# LED_Readout.net
KiCad netlist of a schematic drawn in Altium Designer
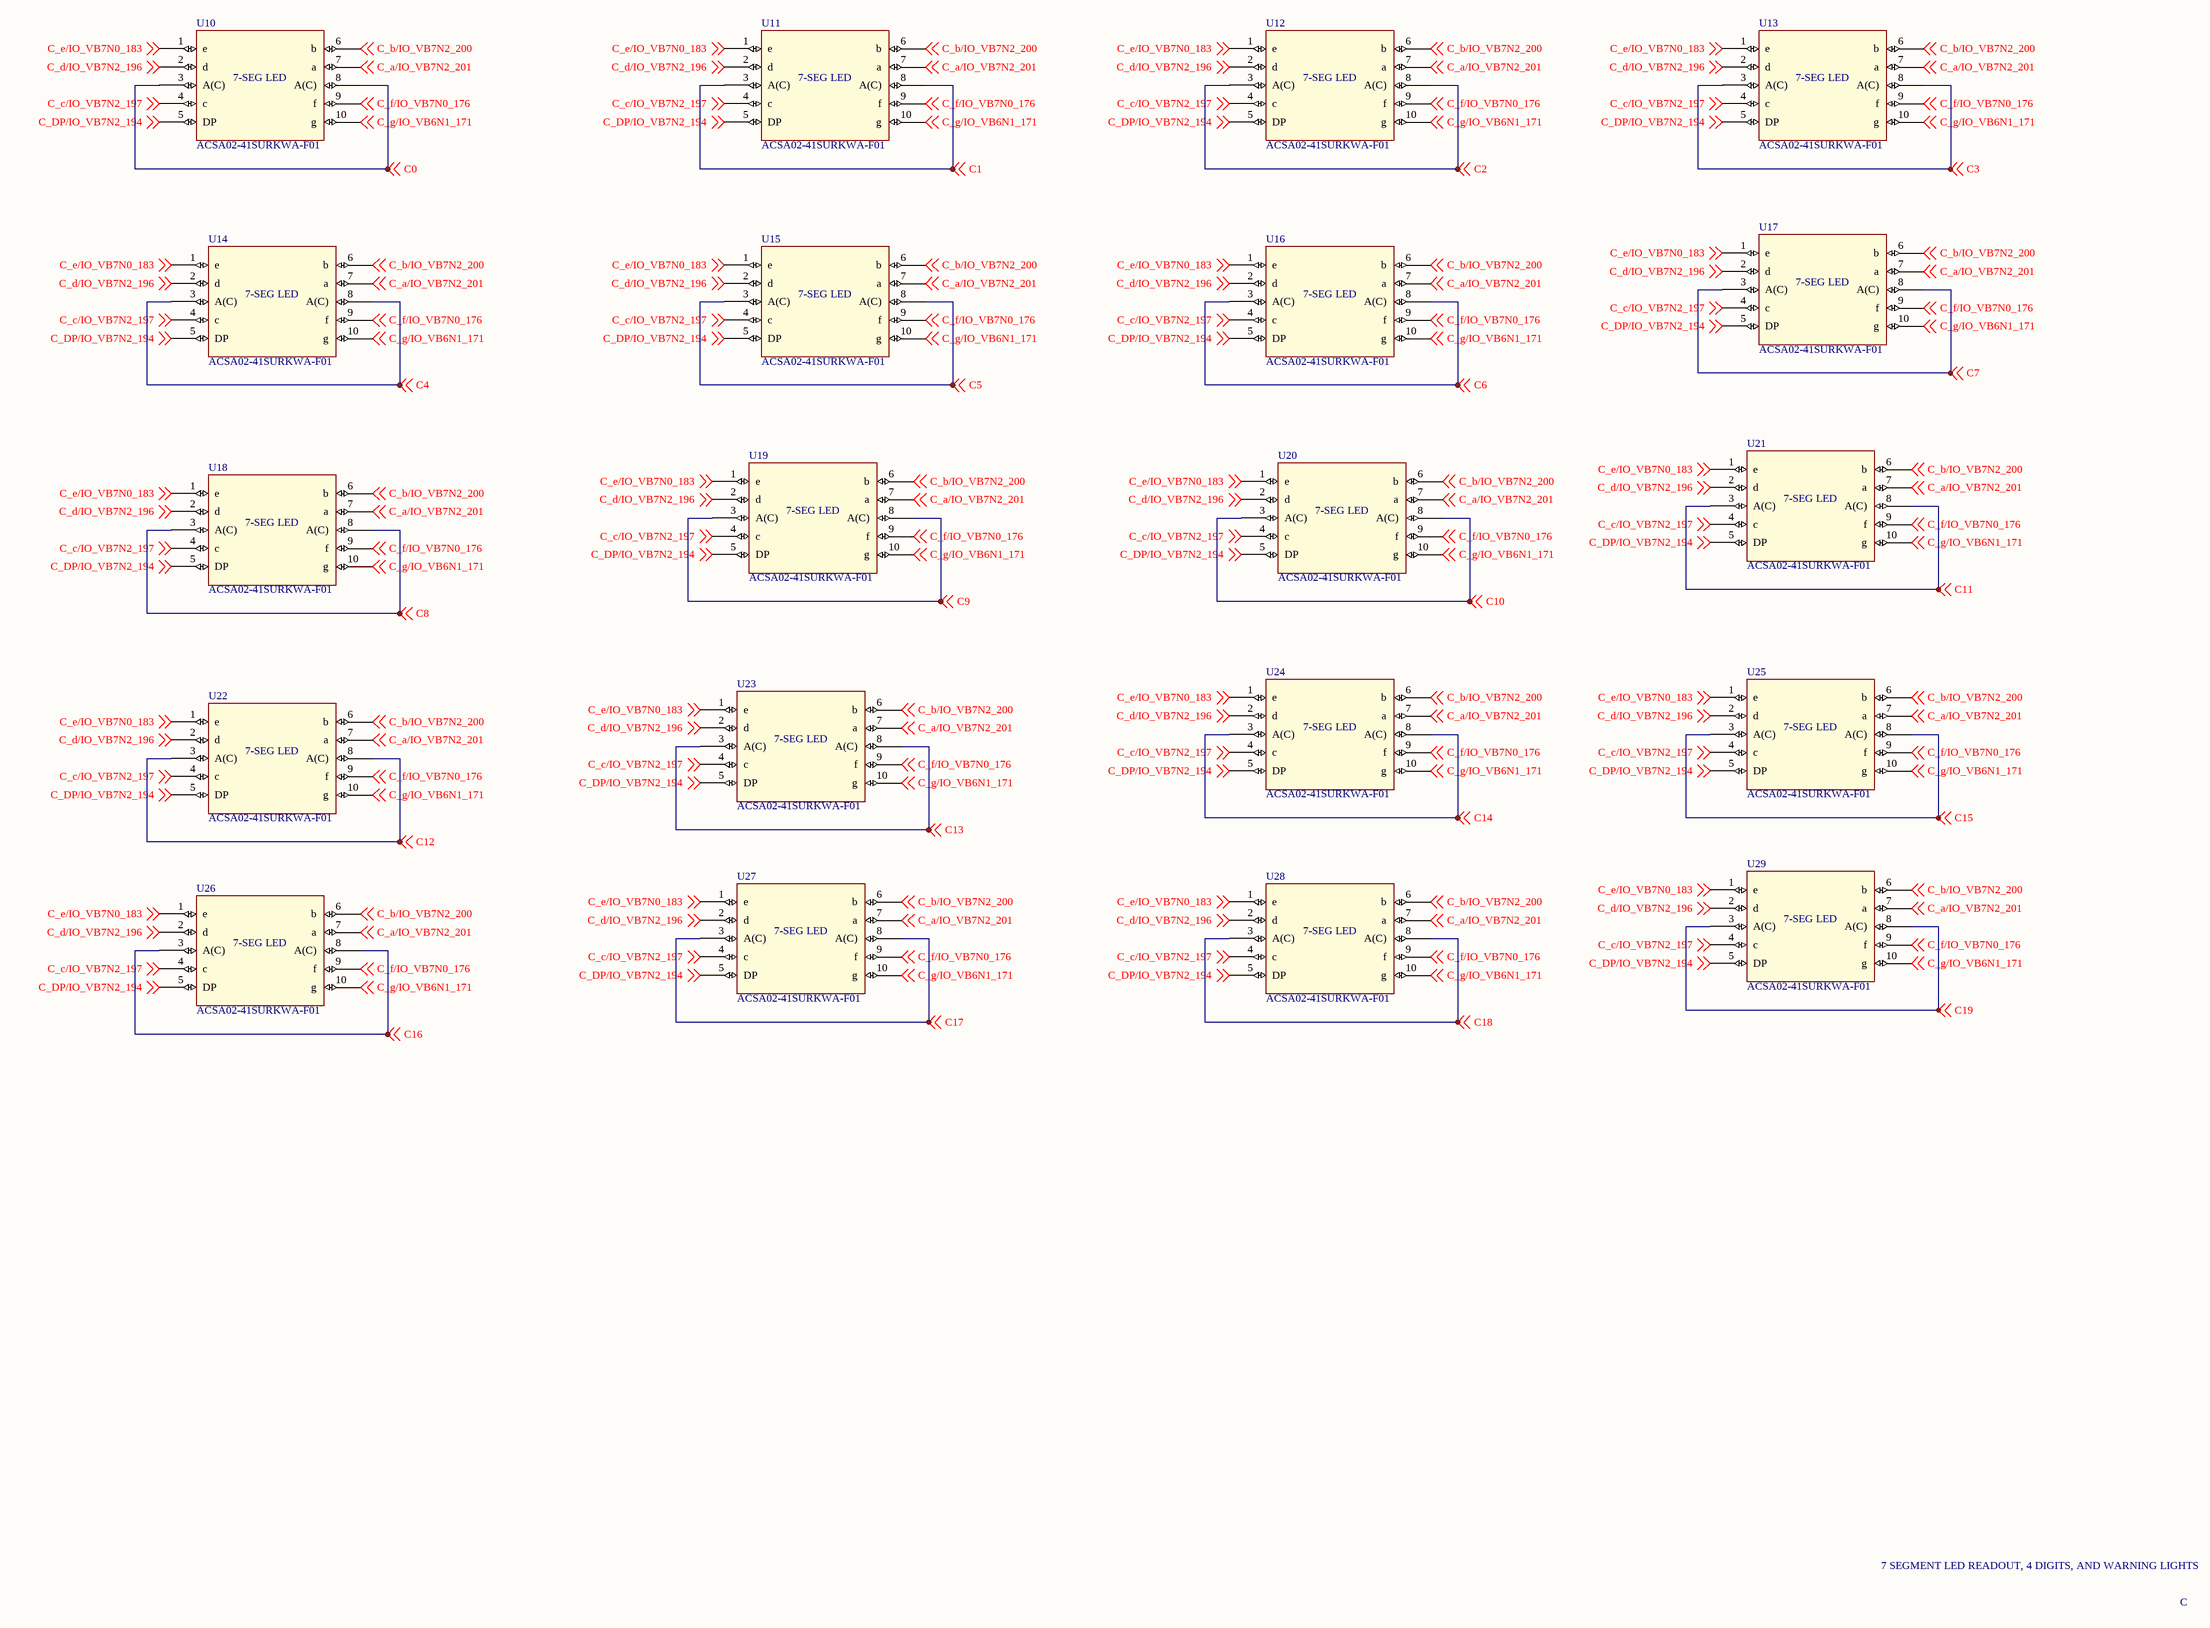
[diagram p0: LED_Readout.SchDoc]

(export (version "E")
  (design (tool "Eeschema 10.0.6"))
  (components
    (comp (ref "U10")
      (value "ACSA02-41SURKWA-F01")
      (footprint "ACSA02-41SURKWA-F01")
      (description "Surface Mount Display")
      (libsource (lib "schematics") (part "ACSA02-41SURKWA-F01"))
    )
    (comp (ref "U11")
      (value "ACSA02-41SURKWA-F01")
      (footprint "ACSA02-41SURKWA-F01")
      (description "Surface Mount Display")
      (libsource (lib "schematics") (part "ACSA02-41SURKWA-F01"))
    )
    (comp (ref "U12")
      (value "ACSA02-41SURKWA-F01")
      (footprint "ACSA02-41SURKWA-F01")
      (description "Surface Mount Display")
      (libsource (lib "schematics") (part "ACSA02-41SURKWA-F01"))
    )
    (comp (ref "U13")
      (value "ACSA02-41SURKWA-F01")
      (footprint "ACSA02-41SURKWA-F01")
      (description "Surface Mount Display")
      (libsource (lib "schematics") (part "ACSA02-41SURKWA-F01"))
    )
    (comp (ref "U14")
      (value "ACSA02-41SURKWA-F01")
      (footprint "ACSA02-41SURKWA-F01")
      (description "Surface Mount Display")
      (libsource (lib "schematics") (part "ACSA02-41SURKWA-F01"))
    )
    (comp (ref "U15")
      (value "ACSA02-41SURKWA-F01")
      (footprint "ACSA02-41SURKWA-F01")
      (description "Surface Mount Display")
      (libsource (lib "schematics") (part "ACSA02-41SURKWA-F01"))
    )
    (comp (ref "U16")
      (value "ACSA02-41SURKWA-F01")
      (footprint "ACSA02-41SURKWA-F01")
      (description "Surface Mount Display")
      (libsource (lib "schematics") (part "ACSA02-41SURKWA-F01"))
    )
    (comp (ref "U17")
      (value "ACSA02-41SURKWA-F01")
      (footprint "ACSA02-41SURKWA-F01")
      (description "Surface Mount Display")
      (libsource (lib "schematics") (part "ACSA02-41SURKWA-F01"))
    )
    (comp (ref "U18")
      (value "ACSA02-41SURKWA-F01")
      (footprint "ACSA02-41SURKWA-F01")
      (description "Surface Mount Display")
      (libsource (lib "schematics") (part "ACSA02-41SURKWA-F01"))
    )
    (comp (ref "U19")
      (value "ACSA02-41SURKWA-F01")
      (footprint "ACSA02-41SURKWA-F01")
      (description "Surface Mount Display")
      (libsource (lib "schematics") (part "ACSA02-41SURKWA-F01"))
    )
    (comp (ref "U20")
      (value "ACSA02-41SURKWA-F01")
      (footprint "ACSA02-41SURKWA-F01")
      (description "Surface Mount Display")
      (libsource (lib "schematics") (part "ACSA02-41SURKWA-F01"))
    )
    (comp (ref "U21")
      (value "ACSA02-41SURKWA-F01")
      (footprint "ACSA02-41SURKWA-F01")
      (description "Surface Mount Display")
      (libsource (lib "schematics") (part "ACSA02-41SURKWA-F01"))
    )
    (comp (ref "U22")
      (value "ACSA02-41SURKWA-F01")
      (footprint "ACSA02-41SURKWA-F01")
      (description "Surface Mount Display")
      (libsource (lib "schematics") (part "ACSA02-41SURKWA-F01"))
    )
    (comp (ref "U23")
      (value "ACSA02-41SURKWA-F01")
      (footprint "ACSA02-41SURKWA-F01")
      (description "Surface Mount Display")
      (libsource (lib "schematics") (part "ACSA02-41SURKWA-F01"))
    )
    (comp (ref "U24")
      (value "ACSA02-41SURKWA-F01")
      (footprint "ACSA02-41SURKWA-F01")
      (description "Surface Mount Display")
      (libsource (lib "schematics") (part "ACSA02-41SURKWA-F01"))
    )
    (comp (ref "U25")
      (value "ACSA02-41SURKWA-F01")
      (footprint "ACSA02-41SURKWA-F01")
      (description "Surface Mount Display")
      (libsource (lib "schematics") (part "ACSA02-41SURKWA-F01"))
    )
    (comp (ref "U26")
      (value "ACSA02-41SURKWA-F01")
      (footprint "ACSA02-41SURKWA-F01")
      (description "Surface Mount Display")
      (libsource (lib "schematics") (part "ACSA02-41SURKWA-F01"))
    )
    (comp (ref "U27")
      (value "ACSA02-41SURKWA-F01")
      (footprint "ACSA02-41SURKWA-F01")
      (description "Surface Mount Display")
      (libsource (lib "schematics") (part "ACSA02-41SURKWA-F01"))
    )
    (comp (ref "U28")
      (value "ACSA02-41SURKWA-F01")
      (footprint "ACSA02-41SURKWA-F01")
      (description "Surface Mount Display")
      (libsource (lib "schematics") (part "ACSA02-41SURKWA-F01"))
    )
    (comp (ref "U29")
      (value "ACSA02-41SURKWA-F01")
      (footprint "ACSA02-41SURKWA-F01")
      (description "Surface Mount Display")
      (libsource (lib "schematics") (part "ACSA02-41SURKWA-F01"))
    )
  )
  (nets
    (net (code "1") (name "C0") (class "Default")
      (node (ref "U10") (pin "3") (pinfunction "A(C)_3") (pintype "bidirectional"))
      (node (ref "U10") (pin "8") (pinfunction "A(C)_8") (pintype "bidirectional"))
    )
    (net (code "2") (name "C1") (class "Default")
      (node (ref "U11") (pin "3") (pinfunction "A(C)_3") (pintype "bidirectional"))
      (node (ref "U11") (pin "8") (pinfunction "A(C)_8") (pintype "bidirectional"))
    )
    (net (code "3") (name "C2") (class "Default")
      (node (ref "U12") (pin "3") (pinfunction "A(C)_3") (pintype "bidirectional"))
      (node (ref "U12") (pin "8") (pinfunction "A(C)_8") (pintype "bidirectional"))
    )
    (net (code "4") (name "C3") (class "Default")
      (node (ref "U13") (pin "3") (pinfunction "A(C)_3") (pintype "bidirectional"))
      (node (ref "U13") (pin "8") (pinfunction "A(C)_8") (pintype "bidirectional"))
    )
    (net (code "5") (name "C4") (class "Default")
      (node (ref "U14") (pin "3") (pinfunction "A(C)_3") (pintype "bidirectional"))
      (node (ref "U14") (pin "8") (pinfunction "A(C)_8") (pintype "bidirectional"))
    )
    (net (code "6") (name "C5") (class "Default")
      (node (ref "U15") (pin "3") (pinfunction "A(C)_3") (pintype "bidirectional"))
      (node (ref "U15") (pin "8") (pinfunction "A(C)_8") (pintype "bidirectional"))
    )
    (net (code "7") (name "C6") (class "Default")
      (node (ref "U16") (pin "3") (pinfunction "A(C)_3") (pintype "bidirectional"))
      (node (ref "U16") (pin "8") (pinfunction "A(C)_8") (pintype "bidirectional"))
    )
    (net (code "8") (name "C7") (class "Default")
      (node (ref "U17") (pin "3") (pinfunction "A(C)_3") (pintype "bidirectional"))
      (node (ref "U17") (pin "8") (pinfunction "A(C)_8") (pintype "bidirectional"))
    )
    (net (code "9") (name "C8") (class "Default")
      (node (ref "U18") (pin "3") (pinfunction "A(C)_3") (pintype "bidirectional"))
      (node (ref "U18") (pin "8") (pinfunction "A(C)_8") (pintype "bidirectional"))
    )
    (net (code "10") (name "C9") (class "Default")
      (node (ref "U19") (pin "3") (pinfunction "A(C)_3") (pintype "bidirectional"))
      (node (ref "U19") (pin "8") (pinfunction "A(C)_8") (pintype "bidirectional"))
    )
    (net (code "11") (name "C10") (class "Default")
      (node (ref "U20") (pin "3") (pinfunction "A(C)_3") (pintype "bidirectional"))
      (node (ref "U20") (pin "8") (pinfunction "A(C)_8") (pintype "bidirectional"))
    )
    (net (code "12") (name "C11") (class "Default")
      (node (ref "U21") (pin "3") (pinfunction "A(C)_3") (pintype "bidirectional"))
      (node (ref "U21") (pin "8") (pinfunction "A(C)_8") (pintype "bidirectional"))
    )
    (net (code "13") (name "C12") (class "Default")
      (node (ref "U22") (pin "3") (pinfunction "A(C)_3") (pintype "bidirectional"))
      (node (ref "U22") (pin "8") (pinfunction "A(C)_8") (pintype "bidirectional"))
    )
    (net (code "14") (name "C13") (class "Default")
      (node (ref "U23") (pin "3") (pinfunction "A(C)_3") (pintype "bidirectional"))
      (node (ref "U23") (pin "8") (pinfunction "A(C)_8") (pintype "bidirectional"))
    )
    (net (code "15") (name "C14") (class "Default")
      (node (ref "U24") (pin "3") (pinfunction "A(C)_3") (pintype "bidirectional"))
      (node (ref "U24") (pin "8") (pinfunction "A(C)_8") (pintype "bidirectional"))
    )
    (net (code "16") (name "C15") (class "Default")
      (node (ref "U25") (pin "3") (pinfunction "A(C)_3") (pintype "bidirectional"))
      (node (ref "U25") (pin "8") (pinfunction "A(C)_8") (pintype "bidirectional"))
    )
    (net (code "17") (name "C16") (class "Default")
      (node (ref "U26") (pin "3") (pinfunction "A(C)_3") (pintype "bidirectional"))
      (node (ref "U26") (pin "8") (pinfunction "A(C)_8") (pintype "bidirectional"))
    )
    (net (code "18") (name "C17") (class "Default")
      (node (ref "U27") (pin "3") (pinfunction "A(C)_3") (pintype "bidirectional"))
      (node (ref "U27") (pin "8") (pinfunction "A(C)_8") (pintype "bidirectional"))
    )
    (net (code "19") (name "C18") (class "Default")
      (node (ref "U28") (pin "3") (pinfunction "A(C)_3") (pintype "bidirectional"))
      (node (ref "U28") (pin "8") (pinfunction "A(C)_8") (pintype "bidirectional"))
    )
    (net (code "20") (name "C19") (class "Default")
      (node (ref "U29") (pin "3") (pinfunction "A(C)_3") (pintype "bidirectional"))
      (node (ref "U29") (pin "8") (pinfunction "A(C)_8") (pintype "bidirectional"))
    )
    (net (code "21") (name "C_DP{slash}IO_VB7N2_194") (class "Default")
      (node (ref "U10") (pin "5") (pinfunction "DP_5") (pintype "bidirectional"))
      (node (ref "U11") (pin "5") (pinfunction "DP_5") (pintype "bidirectional"))
      (node (ref "U12") (pin "5") (pinfunction "DP_5") (pintype "bidirectional"))
      (node (ref "U13") (pin "5") (pinfunction "DP_5") (pintype "bidirectional"))
      (node (ref "U14") (pin "5") (pinfunction "DP_5") (pintype "bidirectional"))
      (node (ref "U15") (pin "5") (pinfunction "DP_5") (pintype "bidirectional"))
      (node (ref "U16") (pin "5") (pinfunction "DP_5") (pintype "bidirectional"))
      (node (ref "U17") (pin "5") (pinfunction "DP_5") (pintype "bidirectional"))
      (node (ref "U18") (pin "5") (pinfunction "DP_5") (pintype "bidirectional"))
      (node (ref "U19") (pin "5") (pinfunction "DP_5") (pintype "bidirectional"))
      (node (ref "U20") (pin "5") (pinfunction "DP_5") (pintype "bidirectional"))
      (node (ref "U21") (pin "5") (pinfunction "DP_5") (pintype "bidirectional"))
      (node (ref "U22") (pin "5") (pinfunction "DP_5") (pintype "bidirectional"))
      (node (ref "U23") (pin "5") (pinfunction "DP_5") (pintype "bidirectional"))
      (node (ref "U24") (pin "5") (pinfunction "DP_5") (pintype "bidirectional"))
      (node (ref "U25") (pin "5") (pinfunction "DP_5") (pintype "bidirectional"))
      (node (ref "U26") (pin "5") (pinfunction "DP_5") (pintype "bidirectional"))
      (node (ref "U27") (pin "5") (pinfunction "DP_5") (pintype "bidirectional"))
      (node (ref "U28") (pin "5") (pinfunction "DP_5") (pintype "bidirectional"))
      (node (ref "U29") (pin "5") (pinfunction "DP_5") (pintype "bidirectional"))
    )
    (net (code "22") (name "C_a{slash}IO_VB7N2_201") (class "Default")
      (node (ref "U10") (pin "7") (pinfunction "a_7") (pintype "bidirectional"))
      (node (ref "U11") (pin "7") (pinfunction "a_7") (pintype "bidirectional"))
      (node (ref "U12") (pin "7") (pinfunction "a_7") (pintype "bidirectional"))
      (node (ref "U13") (pin "7") (pinfunction "a_7") (pintype "bidirectional"))
      (node (ref "U14") (pin "7") (pinfunction "a_7") (pintype "bidirectional"))
      (node (ref "U15") (pin "7") (pinfunction "a_7") (pintype "bidirectional"))
      (node (ref "U16") (pin "7") (pinfunction "a_7") (pintype "bidirectional"))
      (node (ref "U17") (pin "7") (pinfunction "a_7") (pintype "bidirectional"))
      (node (ref "U18") (pin "7") (pinfunction "a_7") (pintype "bidirectional"))
      (node (ref "U19") (pin "7") (pinfunction "a_7") (pintype "bidirectional"))
      (node (ref "U20") (pin "7") (pinfunction "a_7") (pintype "bidirectional"))
      (node (ref "U21") (pin "7") (pinfunction "a_7") (pintype "bidirectional"))
      (node (ref "U22") (pin "7") (pinfunction "a_7") (pintype "bidirectional"))
      (node (ref "U23") (pin "7") (pinfunction "a_7") (pintype "bidirectional"))
      (node (ref "U24") (pin "7") (pinfunction "a_7") (pintype "bidirectional"))
      (node (ref "U25") (pin "7") (pinfunction "a_7") (pintype "bidirectional"))
      (node (ref "U26") (pin "7") (pinfunction "a_7") (pintype "bidirectional"))
      (node (ref "U27") (pin "7") (pinfunction "a_7") (pintype "bidirectional"))
      (node (ref "U28") (pin "7") (pinfunction "a_7") (pintype "bidirectional"))
      (node (ref "U29") (pin "7") (pinfunction "a_7") (pintype "bidirectional"))
    )
    (net (code "23") (name "C_b{slash}IO_VB7N2_200") (class "Default")
      (node (ref "U10") (pin "6") (pinfunction "b_6") (pintype "bidirectional"))
      (node (ref "U11") (pin "6") (pinfunction "b_6") (pintype "bidirectional"))
      (node (ref "U12") (pin "6") (pinfunction "b_6") (pintype "bidirectional"))
      (node (ref "U13") (pin "6") (pinfunction "b_6") (pintype "bidirectional"))
      (node (ref "U14") (pin "6") (pinfunction "b_6") (pintype "bidirectional"))
      (node (ref "U15") (pin "6") (pinfunction "b_6") (pintype "bidirectional"))
      (node (ref "U16") (pin "6") (pinfunction "b_6") (pintype "bidirectional"))
      (node (ref "U17") (pin "6") (pinfunction "b_6") (pintype "bidirectional"))
      (node (ref "U18") (pin "6") (pinfunction "b_6") (pintype "bidirectional"))
      (node (ref "U19") (pin "6") (pinfunction "b_6") (pintype "bidirectional"))
      (node (ref "U20") (pin "6") (pinfunction "b_6") (pintype "bidirectional"))
      (node (ref "U21") (pin "6") (pinfunction "b_6") (pintype "bidirectional"))
      (node (ref "U22") (pin "6") (pinfunction "b_6") (pintype "bidirectional"))
      (node (ref "U23") (pin "6") (pinfunction "b_6") (pintype "bidirectional"))
      (node (ref "U24") (pin "6") (pinfunction "b_6") (pintype "bidirectional"))
      (node (ref "U25") (pin "6") (pinfunction "b_6") (pintype "bidirectional"))
      (node (ref "U26") (pin "6") (pinfunction "b_6") (pintype "bidirectional"))
      (node (ref "U27") (pin "6") (pinfunction "b_6") (pintype "bidirectional"))
      (node (ref "U28") (pin "6") (pinfunction "b_6") (pintype "bidirectional"))
      (node (ref "U29") (pin "6") (pinfunction "b_6") (pintype "bidirectional"))
    )
    (net (code "24") (name "C_c{slash}IO_VB7N2_197") (class "Default")
      (node (ref "U10") (pin "4") (pinfunction "c_4") (pintype "bidirectional"))
      (node (ref "U11") (pin "4") (pinfunction "c_4") (pintype "bidirectional"))
      (node (ref "U12") (pin "4") (pinfunction "c_4") (pintype "bidirectional"))
      (node (ref "U13") (pin "4") (pinfunction "c_4") (pintype "bidirectional"))
      (node (ref "U14") (pin "4") (pinfunction "c_4") (pintype "bidirectional"))
      (node (ref "U15") (pin "4") (pinfunction "c_4") (pintype "bidirectional"))
      (node (ref "U16") (pin "4") (pinfunction "c_4") (pintype "bidirectional"))
      (node (ref "U17") (pin "4") (pinfunction "c_4") (pintype "bidirectional"))
      (node (ref "U18") (pin "4") (pinfunction "c_4") (pintype "bidirectional"))
      (node (ref "U19") (pin "4") (pinfunction "c_4") (pintype "bidirectional"))
      (node (ref "U20") (pin "4") (pinfunction "c_4") (pintype "bidirectional"))
      (node (ref "U21") (pin "4") (pinfunction "c_4") (pintype "bidirectional"))
      (node (ref "U22") (pin "4") (pinfunction "c_4") (pintype "bidirectional"))
      (node (ref "U23") (pin "4") (pinfunction "c_4") (pintype "bidirectional"))
      (node (ref "U24") (pin "4") (pinfunction "c_4") (pintype "bidirectional"))
      (node (ref "U25") (pin "4") (pinfunction "c_4") (pintype "bidirectional"))
      (node (ref "U26") (pin "4") (pinfunction "c_4") (pintype "bidirectional"))
      (node (ref "U27") (pin "4") (pinfunction "c_4") (pintype "bidirectional"))
      (node (ref "U28") (pin "4") (pinfunction "c_4") (pintype "bidirectional"))
      (node (ref "U29") (pin "4") (pinfunction "c_4") (pintype "bidirectional"))
    )
    (net (code "25") (name "C_d{slash}IO_VB7N2_196") (class "Default")
      (node (ref "U10") (pin "2") (pinfunction "d_2") (pintype "bidirectional"))
      (node (ref "U11") (pin "2") (pinfunction "d_2") (pintype "bidirectional"))
      (node (ref "U12") (pin "2") (pinfunction "d_2") (pintype "bidirectional"))
      (node (ref "U13") (pin "2") (pinfunction "d_2") (pintype "bidirectional"))
      (node (ref "U14") (pin "2") (pinfunction "d_2") (pintype "bidirectional"))
      (node (ref "U15") (pin "2") (pinfunction "d_2") (pintype "bidirectional"))
      (node (ref "U16") (pin "2") (pinfunction "d_2") (pintype "bidirectional"))
      (node (ref "U17") (pin "2") (pinfunction "d_2") (pintype "bidirectional"))
      (node (ref "U18") (pin "2") (pinfunction "d_2") (pintype "bidirectional"))
      (node (ref "U19") (pin "2") (pinfunction "d_2") (pintype "bidirectional"))
      (node (ref "U20") (pin "2") (pinfunction "d_2") (pintype "bidirectional"))
      (node (ref "U21") (pin "2") (pinfunction "d_2") (pintype "bidirectional"))
      (node (ref "U22") (pin "2") (pinfunction "d_2") (pintype "bidirectional"))
      (node (ref "U23") (pin "2") (pinfunction "d_2") (pintype "bidirectional"))
      (node (ref "U24") (pin "2") (pinfunction "d_2") (pintype "bidirectional"))
      (node (ref "U25") (pin "2") (pinfunction "d_2") (pintype "bidirectional"))
      (node (ref "U26") (pin "2") (pinfunction "d_2") (pintype "bidirectional"))
      (node (ref "U27") (pin "2") (pinfunction "d_2") (pintype "bidirectional"))
      (node (ref "U28") (pin "2") (pinfunction "d_2") (pintype "bidirectional"))
      (node (ref "U29") (pin "2") (pinfunction "d_2") (pintype "bidirectional"))
    )
    (net (code "26") (name "C_e{slash}IO_VB7N0_183") (class "Default")
      (node (ref "U10") (pin "1") (pinfunction "e_1") (pintype "bidirectional"))
      (node (ref "U11") (pin "1") (pinfunction "e_1") (pintype "bidirectional"))
      (node (ref "U12") (pin "1") (pinfunction "e_1") (pintype "bidirectional"))
      (node (ref "U13") (pin "1") (pinfunction "e_1") (pintype "bidirectional"))
      (node (ref "U14") (pin "1") (pinfunction "e_1") (pintype "bidirectional"))
      (node (ref "U15") (pin "1") (pinfunction "e_1") (pintype "bidirectional"))
      (node (ref "U16") (pin "1") (pinfunction "e_1") (pintype "bidirectional"))
      (node (ref "U17") (pin "1") (pinfunction "e_1") (pintype "bidirectional"))
      (node (ref "U18") (pin "1") (pinfunction "e_1") (pintype "bidirectional"))
      (node (ref "U19") (pin "1") (pinfunction "e_1") (pintype "bidirectional"))
      (node (ref "U20") (pin "1") (pinfunction "e_1") (pintype "bidirectional"))
      (node (ref "U21") (pin "1") (pinfunction "e_1") (pintype "bidirectional"))
      (node (ref "U22") (pin "1") (pinfunction "e_1") (pintype "bidirectional"))
      (node (ref "U23") (pin "1") (pinfunction "e_1") (pintype "bidirectional"))
      (node (ref "U24") (pin "1") (pinfunction "e_1") (pintype "bidirectional"))
      (node (ref "U25") (pin "1") (pinfunction "e_1") (pintype "bidirectional"))
      (node (ref "U26") (pin "1") (pinfunction "e_1") (pintype "bidirectional"))
      (node (ref "U27") (pin "1") (pinfunction "e_1") (pintype "bidirectional"))
      (node (ref "U28") (pin "1") (pinfunction "e_1") (pintype "bidirectional"))
      (node (ref "U29") (pin "1") (pinfunction "e_1") (pintype "bidirectional"))
    )
    (net (code "27") (name "C_f{slash}IO_VB7N0_176") (class "Default")
      (node (ref "U10") (pin "9") (pinfunction "f_9") (pintype "bidirectional"))
      (node (ref "U11") (pin "9") (pinfunction "f_9") (pintype "bidirectional"))
      (node (ref "U12") (pin "9") (pinfunction "f_9") (pintype "bidirectional"))
      (node (ref "U13") (pin "9") (pinfunction "f_9") (pintype "bidirectional"))
      (node (ref "U14") (pin "9") (pinfunction "f_9") (pintype "bidirectional"))
      (node (ref "U15") (pin "9") (pinfunction "f_9") (pintype "bidirectional"))
      (node (ref "U16") (pin "9") (pinfunction "f_9") (pintype "bidirectional"))
      (node (ref "U17") (pin "9") (pinfunction "f_9") (pintype "bidirectional"))
      (node (ref "U18") (pin "9") (pinfunction "f_9") (pintype "bidirectional"))
      (node (ref "U19") (pin "9") (pinfunction "f_9") (pintype "bidirectional"))
      (node (ref "U20") (pin "9") (pinfunction "f_9") (pintype "bidirectional"))
      (node (ref "U21") (pin "9") (pinfunction "f_9") (pintype "bidirectional"))
      (node (ref "U22") (pin "9") (pinfunction "f_9") (pintype "bidirectional"))
      (node (ref "U23") (pin "9") (pinfunction "f_9") (pintype "bidirectional"))
      (node (ref "U24") (pin "9") (pinfunction "f_9") (pintype "bidirectional"))
      (node (ref "U25") (pin "9") (pinfunction "f_9") (pintype "bidirectional"))
      (node (ref "U26") (pin "9") (pinfunction "f_9") (pintype "bidirectional"))
      (node (ref "U27") (pin "9") (pinfunction "f_9") (pintype "bidirectional"))
      (node (ref "U28") (pin "9") (pinfunction "f_9") (pintype "bidirectional"))
      (node (ref "U29") (pin "9") (pinfunction "f_9") (pintype "bidirectional"))
    )
    (net (code "28") (name "C_g{slash}IO_VB6N1_171") (class "Default")
      (node (ref "U10") (pin "10") (pinfunction "g_10") (pintype "bidirectional"))
      (node (ref "U11") (pin "10") (pinfunction "g_10") (pintype "bidirectional"))
      (node (ref "U12") (pin "10") (pinfunction "g_10") (pintype "bidirectional"))
      (node (ref "U13") (pin "10") (pinfunction "g_10") (pintype "bidirectional"))
      (node (ref "U14") (pin "10") (pinfunction "g_10") (pintype "bidirectional"))
      (node (ref "U15") (pin "10") (pinfunction "g_10") (pintype "bidirectional"))
      (node (ref "U16") (pin "10") (pinfunction "g_10") (pintype "bidirectional"))
      (node (ref "U17") (pin "10") (pinfunction "g_10") (pintype "bidirectional"))
      (node (ref "U18") (pin "10") (pinfunction "g_10") (pintype "bidirectional"))
      (node (ref "U19") (pin "10") (pinfunction "g_10") (pintype "bidirectional"))
      (node (ref "U20") (pin "10") (pinfunction "g_10") (pintype "bidirectional"))
      (node (ref "U21") (pin "10") (pinfunction "g_10") (pintype "bidirectional"))
      (node (ref "U22") (pin "10") (pinfunction "g_10") (pintype "bidirectional"))
      (node (ref "U23") (pin "10") (pinfunction "g_10") (pintype "bidirectional"))
      (node (ref "U24") (pin "10") (pinfunction "g_10") (pintype "bidirectional"))
      (node (ref "U25") (pin "10") (pinfunction "g_10") (pintype "bidirectional"))
      (node (ref "U26") (pin "10") (pinfunction "g_10") (pintype "bidirectional"))
      (node (ref "U27") (pin "10") (pinfunction "g_10") (pintype "bidirectional"))
      (node (ref "U28") (pin "10") (pinfunction "g_10") (pintype "bidirectional"))
      (node (ref "U29") (pin "10") (pinfunction "g_10") (pintype "bidirectional"))
    )
  )
)
